# ELEKTRA-PMIC_v0_2-Half_frame_shield_for_.net
KiCad netlist of a schematic drawn in EAGLE
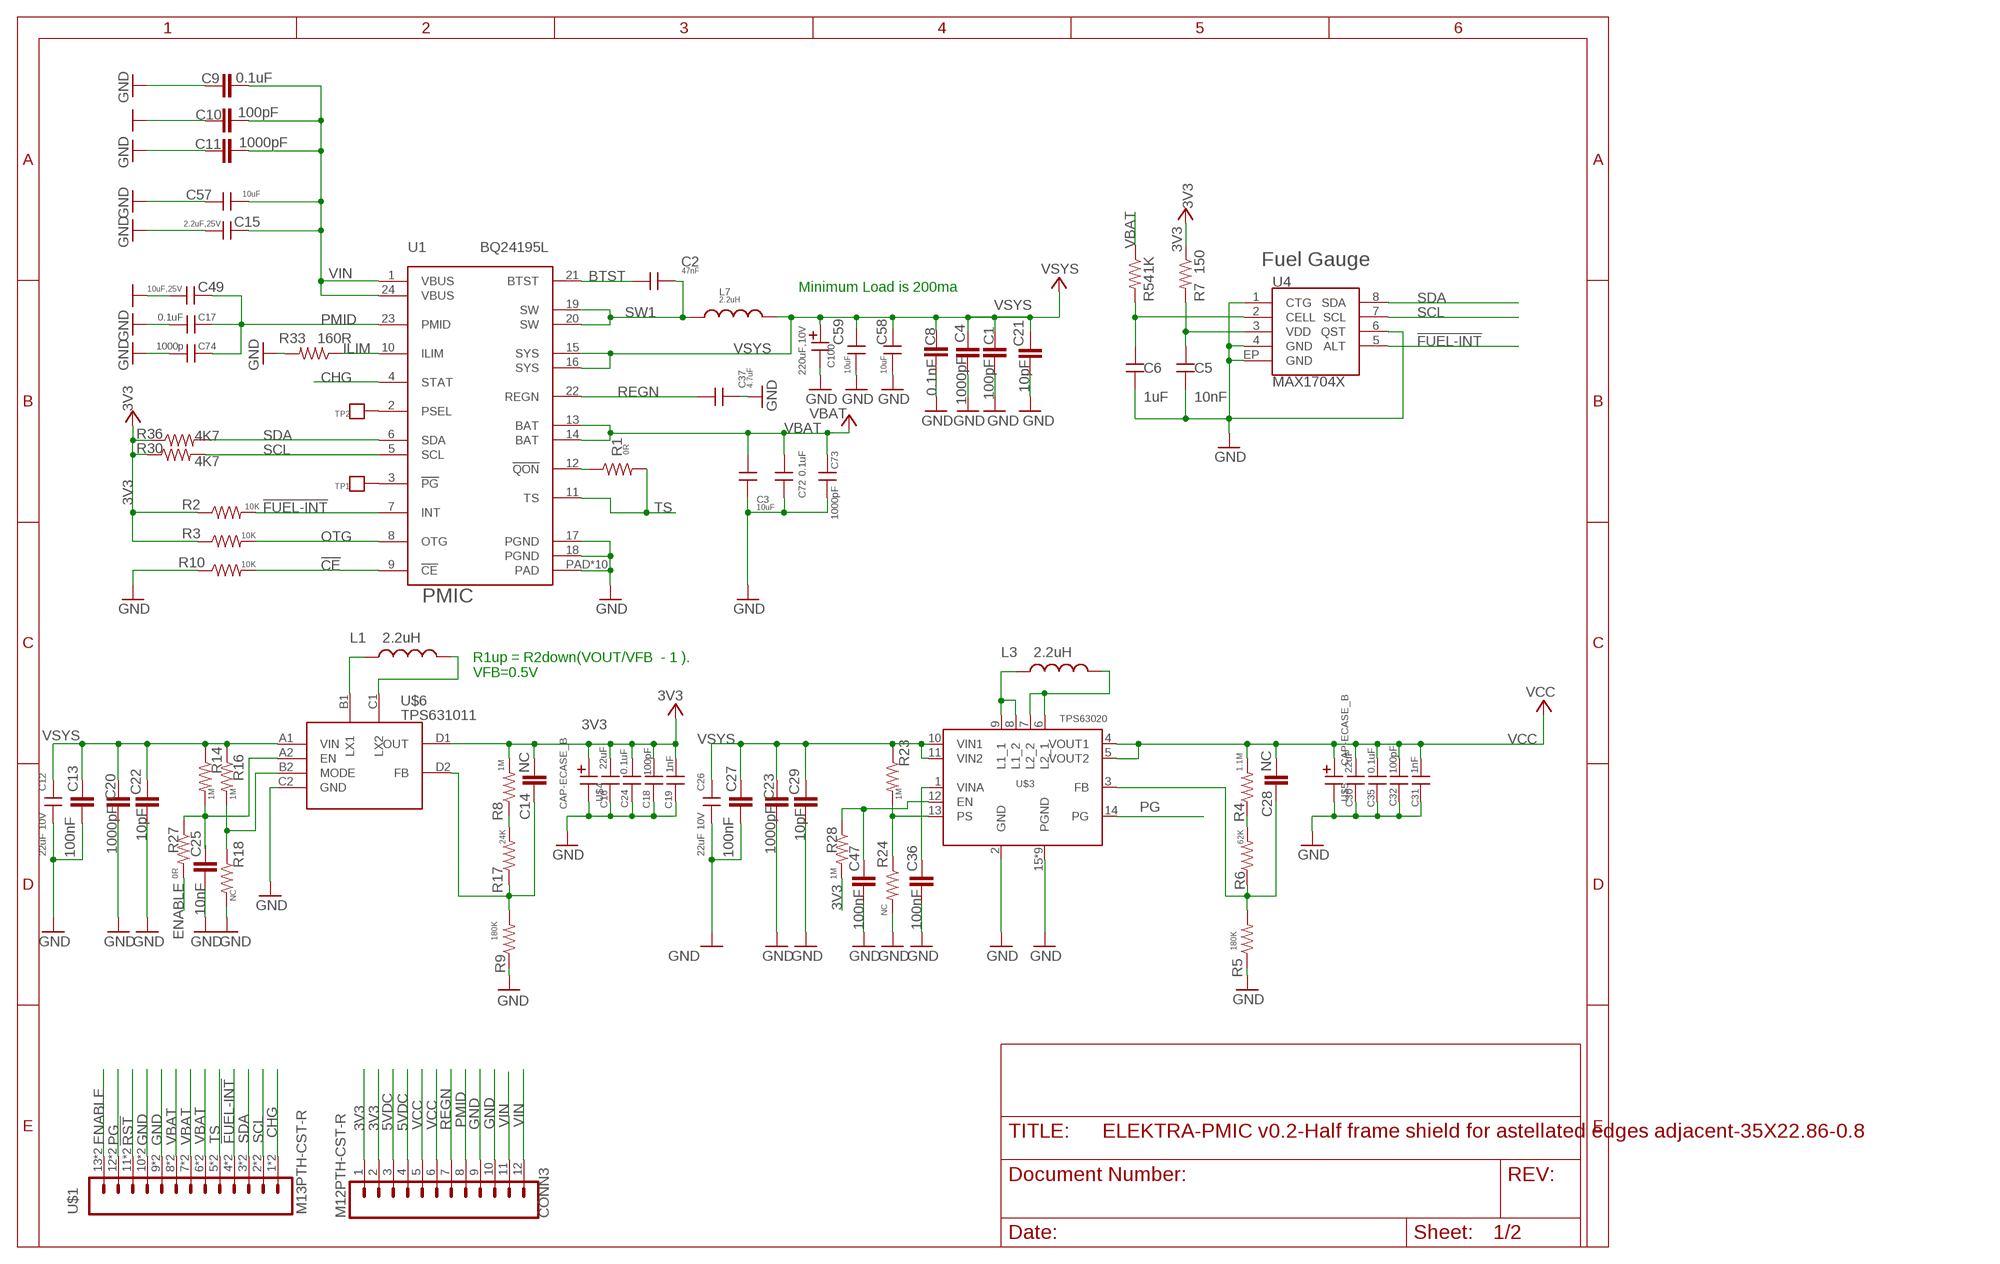
[diagram p0: schematic, sheet 1]

(export (version "E")
  (design (tool "Eeschema 10.0.6"))
  (components
    (comp (ref "C1")
      (value "100pF")
      (footprint "eagle-import:C0402_B")
      (libsource (lib "eagle-import") (part "CAP_1"))
    )
    (comp (ref "C2")
      (value "47nF")
      (footprint "eagle-import:C-0402")
      (libsource (lib "eagle-import") (part "particle SZ_CAP0402"))
    )
    (comp (ref "C3")
      (value "10uF")
      (footprint "eagle-import:C0603")
      (libsource (lib "eagle-import") (part "particle SZ_CAPC0603"))
    )
    (comp (ref "C4")
      (value "1000pF")
      (footprint "eagle-import:C0402_B")
      (libsource (lib "eagle-import") (part "CAP_1"))
    )
    (comp (ref "C5")
      (value "10nF")
      (footprint "eagle-import:C0402")
      (libsource (lib "eagle-import") (part "particle SZ_CAP0402A"))
    )
    (comp (ref "C6")
      (value "1uF")
      (footprint "eagle-import:C0402")
      (libsource (lib "eagle-import") (part "particle SZ_CAP0402A"))
    )
    (comp (ref "C8")
      (value "0.1nF")
      (footprint "eagle-import:C0402_B")
      (libsource (lib "eagle-import") (part "CAP_1"))
    )
    (comp (ref "C9")
      (value "0.1uF")
      (footprint "eagle-import:C0402_B")
      (libsource (lib "eagle-import") (part "CAP_1"))
    )
    (comp (ref "C10")
      (value "100pF")
      (footprint "eagle-import:C0402_B")
      (libsource (lib "eagle-import") (part "CAP_1"))
    )
    (comp (ref "C11")
      (value "1000pF")
      (footprint "eagle-import:C0402_B")
      (libsource (lib "eagle-import") (part "CAP_1"))
    )
    (comp (ref "C12")
      (value "22uF 10V")
      (footprint "eagle-import:C0805")
      (libsource (lib "eagle-import") (part "particle SZ_21650216_CAPC0805"))
    )
    (comp (ref "C13")
      (value "100nF")
      (footprint "eagle-import:C0402_B")
      (libsource (lib "eagle-import") (part "CAP_1"))
    )
    (comp (ref "C14")
      (value "NC")
      (footprint "eagle-import:C0402_B")
      (libsource (lib "eagle-import") (part "CAP_1"))
    )
    (comp (ref "C15")
      (value "2.2uF,25V")
      (footprint "eagle-import:C-0603A")
      (libsource (lib "eagle-import") (part "particle SZ_CAP0603A"))
    )
    (comp (ref "C16")
      (value "22uF")
      (footprint "eagle-import:C-0603A")
      (libsource (lib "eagle-import") (part "particle SZ_21650216_CAP0603A"))
    )
    (comp (ref "C17")
      (value "0.1uF")
      (footprint "eagle-import:C0402")
      (libsource (lib "eagle-import") (part "CAP0402A"))
    )
    (comp (ref "C18")
      (value "100pF")
      (footprint "eagle-import:C0402")
      (libsource (lib "eagle-import") (part "particle SZ_CAP0402A"))
    )
    (comp (ref "C19")
      (value "1nF")
      (footprint "eagle-import:C0402")
      (libsource (lib "eagle-import") (part "particle SZ_CAP0402A"))
    )
    (comp (ref "C20")
      (value "1000pF")
      (footprint "eagle-import:C0402_B")
      (libsource (lib "eagle-import") (part "CAP_1"))
    )
    (comp (ref "C21")
      (value "10pF")
      (footprint "eagle-import:C0402_B")
      (libsource (lib "eagle-import") (part "CAP_1"))
    )
    (comp (ref "C22")
      (value "10pF")
      (footprint "eagle-import:C0402_B")
      (libsource (lib "eagle-import") (part "CAP_1"))
    )
    (comp (ref "C23")
      (value "1000pF")
      (footprint "eagle-import:C0402_B")
      (libsource (lib "eagle-import") (part "CAP_1"))
    )
    (comp (ref "C24")
      (value "0.1uF")
      (footprint "eagle-import:C0402")
      (libsource (lib "eagle-import") (part "particle SZ_CAP0402A"))
    )
    (comp (ref "C25")
      (value "10nF")
      (footprint "eagle-import:C0402_B")
      (libsource (lib "eagle-import") (part "CAP_1"))
    )
    (comp (ref "C26")
      (value "22uF 10V")
      (footprint "eagle-import:C0805")
      (libsource (lib "eagle-import") (part "particle SZ_21650216_CAPC0805"))
    )
    (comp (ref "C27")
      (value "100nF")
      (footprint "eagle-import:C0402_B")
      (libsource (lib "eagle-import") (part "CAP_1"))
    )
    (comp (ref "C28")
      (value "NC")
      (footprint "eagle-import:C0402_B")
      (libsource (lib "eagle-import") (part "CAP_1"))
    )
    (comp (ref "C29")
      (value "10pF")
      (footprint "eagle-import:C0402_B")
      (libsource (lib "eagle-import") (part "CAP_1"))
    )
    (comp (ref "C30")
      (value "22uF")
      (footprint "eagle-import:C-0603A")
      (libsource (lib "eagle-import") (part "particle SZ_21650216_CAP0603A"))
    )
    (comp (ref "C31")
      (value "1nF")
      (footprint "eagle-import:C0402")
      (libsource (lib "eagle-import") (part "particle SZ_CAP0402A"))
    )
    (comp (ref "C32")
      (value "100pF")
      (footprint "eagle-import:C0402")
      (libsource (lib "eagle-import") (part "particle SZ_CAP0402A"))
    )
    (comp (ref "C35")
      (value "0.1uF")
      (footprint "eagle-import:C0402")
      (libsource (lib "eagle-import") (part "particle SZ_CAP0402A"))
    )
    (comp (ref "C36")
      (value "100nF")
      (footprint "eagle-import:C0402_B")
      (libsource (lib "eagle-import") (part "CAP_1"))
    )
    (comp (ref "C37")
      (value "4.7uF")
      (footprint "eagle-import:C0402")
      (libsource (lib "eagle-import") (part "particle SZ_CAP0402A"))
    )
    (comp (ref "C47")
      (value "100nF")
      (footprint "eagle-import:C0402_B")
      (libsource (lib "eagle-import") (part "CAP_1"))
    )
    (comp (ref "C49")
      (value "10uF,25V")
      (footprint "eagle-import:C-0603A")
      (libsource (lib "eagle-import") (part "particle SZ_CAP0603A"))
    )
    (comp (ref "C57")
      (value "10uF")
      (footprint "eagle-import:C-0603A")
      (libsource (lib "eagle-import") (part "particle SZ_CAP0603A"))
    )
    (comp (ref "C58")
      (value "10uF")
      (footprint "eagle-import:C-0603A")
      (libsource (lib "eagle-import") (part "particle SZ_CAP0603A"))
    )
    (comp (ref "C59")
      (value "10uF")
      (footprint "eagle-import:C-0603A")
      (libsource (lib "eagle-import") (part "particle SZ_CAP0603A"))
    )
    (comp (ref "C72")
      (value "0.1uF")
      (footprint "eagle-import:C-0402")
      (libsource (lib "eagle-import") (part "particle SZ_CAP0402"))
    )
    (comp (ref "C73")
      (value "1000pF")
      (footprint "eagle-import:C-0402")
      (libsource (lib "eagle-import") (part "particle SZ_CAP0402"))
    )
    (comp (ref "C74")
      (value "1000p")
      (footprint "eagle-import:C-0402")
      (libsource (lib "eagle-import") (part "particle SZ_CAP0402"))
    )
    (comp (ref "C100")
      (value "220uF,10V")
      (footprint "eagle-import:CASE-B")
      (libsource (lib "eagle-import") (part "CAP-ECASE_B"))
    )
    (comp (ref "CONN3")
      (value "M12PTH-CST-R")
      (footprint "eagle-import:1X12-CASTELLATED")
      (libsource (lib "eagle-import") (part "M12PTH-CST-R"))
    )
    (comp (ref "L1")
      (value "2.2uH")
      (footprint "eagle-import:INDUCTOR-VLS-E")
      (libsource (lib "eagle-import") (part "INDUCTOR-SPARKFUNVLS3012ET-4R7M"))
    )
    (comp (ref "L3")
      (value "2.2uH")
      (footprint "eagle-import:INDUCTOR-VLS-E")
      (libsource (lib "eagle-import") (part "INDUCTOR-SPARKFUNVLS3012ET-4R7M"))
    )
    (comp (ref "L7")
      (value "2.2uH")
      (footprint "eagle-import:INDUCTOR-4040")
      (libsource (lib "eagle-import") (part "INDUCTORI"))
    )
    (comp (ref "R1")
      (value "0R")
      (footprint "eagle-import:R0402_B")
      (libsource (lib "eagle-import") (part "Spark_R-US_"))
    )
    (comp (ref "R2")
      (value "10K")
      (footprint "eagle-import:R0402_B")
      (libsource (lib "eagle-import") (part "Spark_R-US_"))
    )
    (comp (ref "R3")
      (value "10K")
      (footprint "eagle-import:R0402_B")
      (libsource (lib "eagle-import") (part "Spark_R-US_"))
    )
    (comp (ref "R4")
      (value "1.1M")
      (footprint "eagle-import:R0402_B")
      (libsource (lib "eagle-import") (part "Spark_R-US_"))
    )
    (comp (ref "R5")
      (value "180K")
      (footprint "eagle-import:R0402_B")
      (libsource (lib "eagle-import") (part "Spark_R-US_"))
    )
    (comp (ref "R6")
      (value "62K")
      (footprint "eagle-import:R0402_B")
      (libsource (lib "eagle-import") (part "Spark_R-US_"))
    )
    (comp (ref "R7")
      (value "150")
      (footprint "eagle-import:R0402_B")
      (libsource (lib "eagle-import") (part "R-US_"))
    )
    (comp (ref "R8")
      (value "1M")
      (footprint "eagle-import:R0402_B")
      (libsource (lib "eagle-import") (part "Spark_R-US_"))
    )
    (comp (ref "R9")
      (value "180K")
      (footprint "eagle-import:R0402_B")
      (libsource (lib "eagle-import") (part "Spark_R-US_"))
    )
    (comp (ref "R10")
      (value "10K")
      (footprint "eagle-import:R0402_B")
      (libsource (lib "eagle-import") (part "Spark_R-US_"))
    )
    (comp (ref "R14")
      (value "1M")
      (footprint "eagle-import:R0402_B")
      (libsource (lib "eagle-import") (part "Spark_R-US_"))
    )
    (comp (ref "R16")
      (value "1M")
      (footprint "eagle-import:R0402_B")
      (libsource (lib "eagle-import") (part "Spark_R-US_"))
    )
    (comp (ref "R17")
      (value "24K")
      (footprint "eagle-import:R0402_B")
      (libsource (lib "eagle-import") (part "Spark_R-US_"))
    )
    (comp (ref "R18")
      (value "NC")
      (footprint "eagle-import:R0402_B")
      (libsource (lib "eagle-import") (part "Spark_R-US_"))
    )
    (comp (ref "R23")
      (value "1M")
      (footprint "eagle-import:R0402_B")
      (libsource (lib "eagle-import") (part "Spark_R-US_"))
    )
    (comp (ref "R24")
      (value "NC")
      (footprint "eagle-import:R0402_B")
      (libsource (lib "eagle-import") (part "Spark_R-US_"))
    )
    (comp (ref "R27")
      (value "0R")
      (footprint "eagle-import:R0402_B")
      (libsource (lib "eagle-import") (part "Spark_R-US_"))
    )
    (comp (ref "R28")
      (value "1M")
      (footprint "eagle-import:R0402_B")
      (libsource (lib "eagle-import") (part "Spark_R-US_"))
    )
    (comp (ref "R30")
      (value "4K7")
      (footprint "eagle-import:R0402_B")
      (libsource (lib "eagle-import") (part "R-US_"))
    )
    (comp (ref "R33")
      (value "160R")
      (footprint "eagle-import:R0402_B")
      (libsource (lib "eagle-import") (part "R-US_"))
    )
    (comp (ref "R36")
      (value "4K7")
      (footprint "eagle-import:R0402_B")
      (libsource (lib "eagle-import") (part "R-US_"))
    )
    (comp (ref "R54")
      (value "1K")
      (footprint "eagle-import:R0402_B")
      (libsource (lib "eagle-import") (part "R-US_"))
    )
    (comp (ref "TP1")
      (value "TP")
      (footprint "eagle-import:TP0.7MM")
      (libsource (lib "eagle-import") (part "TP"))
    )
    (comp (ref "TP2")
      (value "TP")
      (footprint "eagle-import:TP0.7MM")
      (libsource (lib "eagle-import") (part "TP"))
    )
    (comp (ref "U$1")
      (value "M13PTH-CST-R")
      (footprint "eagle-import:1X13-CASTELLATED")
      (libsource (lib "eagle-import") (part "M13PTH-CST-R"))
    )
    (comp (ref "U$3")
      (value "TPS63020")
      (footprint "eagle-import:TPS63020")
      (libsource (lib "eagle-import") (part "TPS63020"))
    )
    (comp (ref "U$4")
      (value "CAP-ECASE_B")
      (footprint "eagle-import:CASE-B")
      (libsource (lib "eagle-import") (part "CAP-ECASE_B"))
    )
    (comp (ref "U$5")
      (value "CAP-ECASE_B")
      (footprint "eagle-import:CASE-B")
      (libsource (lib "eagle-import") (part "CAP-ECASE_B"))
    )
    (comp (ref "U$6")
      (value "TPS631011")
      (footprint "eagle-import:DSBGA")
      (libsource (lib "eagle-import") (part "TPS631010"))
    )
    (comp (ref "U1")
      (value "BQ24195L")
      (footprint "eagle-import:QFN24")
      (libsource (lib "eagle-import") (part "BQ24298RTWR"))
    )
    (comp (ref "U4")
      (value "MAX1704X")
      (footprint "eagle-import:TDFN-8")
      (libsource (lib "eagle-import") (part "MAX1704X"))
    )
  )
  (nets
    (net (code "1") (name "3V3") (class "Default")
      (node (ref "C14") (pin "2") (pinfunction "P$2_2") (pintype "passive"))
      (node (ref "C16") (pin "1") (pinfunction "1_1") (pintype "bidirectional"))
      (node (ref "C18") (pin "1") (pinfunction "1_1") (pintype "bidirectional"))
      (node (ref "C19") (pin "1") (pinfunction "1_1") (pintype "bidirectional"))
      (node (ref "C24") (pin "1") (pinfunction "1_1") (pintype "bidirectional"))
      (node (ref "CONN3") (pin "1") (pinfunction "1_1") (pintype "passive"))
      (node (ref "CONN3") (pin "2") (pinfunction "2_2") (pintype "passive"))
      (node (ref "R2") (pin "1") (pinfunction "1_1") (pintype "passive"))
      (node (ref "R28") (pin "2") (pinfunction "2_2") (pintype "passive"))
      (node (ref "R3") (pin "1") (pinfunction "1_1") (pintype "passive"))
      (node (ref "R30") (pin "1") (pinfunction "1_1") (pintype "passive"))
      (node (ref "R36") (pin "1") (pinfunction "1_1") (pintype "passive"))
      (node (ref "R7") (pin "1") (pinfunction "1_1") (pintype "passive"))
      (node (ref "R8") (pin "2") (pinfunction "2_2") (pintype "passive"))
      (node (ref "U$4") (pin "P$1") (pinfunction "1_P$1") (pintype "bidirectional"))
      (node (ref "U$6") (pin "D1") (pinfunction "OUT_D1") (pintype "bidirectional"))
    )
    (net (code "2") (name "5VDC") (class "Default")
      (node (ref "CONN3") (pin "3") (pinfunction "3_3") (pintype "passive"))
      (node (ref "CONN3") (pin "4") (pinfunction "4_4") (pintype "passive"))
    )
    (net (code "3") (name "BTST") (class "Default")
      (node (ref "C2") (pin "1") (pinfunction "1_1") (pintype "bidirectional"))
      (node (ref "U1") (pin "21") (pinfunction "BTST_21") (pintype "bidirectional"))
    )
    (net (code "4") (name "CHG") (class "Default")
      (node (ref "U$1") (pin "1") (pinfunction "1_1") (pintype "passive"))
      (node (ref "U$1") (pin "@1") (pinfunction "1_@1") (pintype "passive"))
      (node (ref "U1") (pin "4") (pinfunction "STAT_4") (pintype "bidirectional"))
    )
    (net (code "5") (name "ENABLE") (class "Default")
      (node (ref "R27") (pin "2") (pinfunction "2_2") (pintype "passive"))
      (node (ref "U$1") (pin "13") (pinfunction "13_13") (pintype "passive"))
      (node (ref "U$1") (pin "@13") (pinfunction "13_@13") (pintype "passive"))
    )
    (net (code "6") (name "GND") (class "Default")
      (node (ref "C1") (pin "1") (pinfunction "P$1_1") (pintype "passive"))
      (node (ref "C10") (pin "1") (pinfunction "P$1_1") (pintype "passive"))
      (node (ref "C100") (pin "P$2") (pinfunction "2_P$2") (pintype "bidirectional"))
      (node (ref "C11") (pin "1") (pinfunction "P$1_1") (pintype "passive"))
      (node (ref "C12") (pin "2") (pinfunction "2_2") (pintype "bidirectional"))
      (node (ref "C13") (pin "1") (pinfunction "P$1_1") (pintype "passive"))
      (node (ref "C15") (pin "2") (pinfunction "2_2") (pintype "bidirectional"))
      (node (ref "C16") (pin "2") (pinfunction "2_2") (pintype "bidirectional"))
      (node (ref "C17") (pin "1") (pinfunction "1_1") (pintype "bidirectional"))
      (node (ref "C18") (pin "2") (pinfunction "2_2") (pintype "bidirectional"))
      (node (ref "C19") (pin "2") (pinfunction "2_2") (pintype "bidirectional"))
      (node (ref "C20") (pin "1") (pinfunction "P$1_1") (pintype "passive"))
      (node (ref "C21") (pin "1") (pinfunction "P$1_1") (pintype "passive"))
      (node (ref "C22") (pin "1") (pinfunction "P$1_1") (pintype "passive"))
      (node (ref "C23") (pin "1") (pinfunction "P$1_1") (pintype "passive"))
      (node (ref "C24") (pin "2") (pinfunction "2_2") (pintype "bidirectional"))
      (node (ref "C25") (pin "1") (pinfunction "P$1_1") (pintype "passive"))
      (node (ref "C26") (pin "2") (pinfunction "2_2") (pintype "bidirectional"))
      (node (ref "C27") (pin "1") (pinfunction "P$1_1") (pintype "passive"))
      (node (ref "C29") (pin "1") (pinfunction "P$1_1") (pintype "passive"))
      (node (ref "C3") (pin "2") (pinfunction "2_2") (pintype "bidirectional"))
      (node (ref "C30") (pin "2") (pinfunction "2_2") (pintype "bidirectional"))
      (node (ref "C31") (pin "2") (pinfunction "2_2") (pintype "bidirectional"))
      (node (ref "C32") (pin "2") (pinfunction "2_2") (pintype "bidirectional"))
      (node (ref "C35") (pin "2") (pinfunction "2_2") (pintype "bidirectional"))
      (node (ref "C36") (pin "1") (pinfunction "P$1_1") (pintype "passive"))
      (node (ref "C37") (pin "2") (pinfunction "2_2") (pintype "bidirectional"))
      (node (ref "C4") (pin "1") (pinfunction "P$1_1") (pintype "passive"))
      (node (ref "C47") (pin "1") (pinfunction "P$1_1") (pintype "passive"))
      (node (ref "C49") (pin "2") (pinfunction "2_2") (pintype "bidirectional"))
      (node (ref "C5") (pin "2") (pinfunction "2_2") (pintype "bidirectional"))
      (node (ref "C57") (pin "2") (pinfunction "2_2") (pintype "bidirectional"))
      (node (ref "C58") (pin "2") (pinfunction "2_2") (pintype "bidirectional"))
      (node (ref "C59") (pin "2") (pinfunction "2_2") (pintype "bidirectional"))
      (node (ref "C6") (pin "2") (pinfunction "2_2") (pintype "bidirectional"))
      (node (ref "C72") (pin "2") (pinfunction "2_2") (pintype "bidirectional"))
      (node (ref "C73") (pin "2") (pinfunction "2_2") (pintype "bidirectional"))
      (node (ref "C74") (pin "1") (pinfunction "1_1") (pintype "bidirectional"))
      (node (ref "C8") (pin "1") (pinfunction "P$1_1") (pintype "passive"))
      (node (ref "C9") (pin "1") (pinfunction "P$1_1") (pintype "passive"))
      (node (ref "CONN3") (pin "10") (pinfunction "10_10") (pintype "passive"))
      (node (ref "CONN3") (pin "9") (pinfunction "9_9") (pintype "passive"))
      (node (ref "R10") (pin "1") (pinfunction "1_1") (pintype "passive"))
      (node (ref "R18") (pin "2") (pinfunction "2_2") (pintype "passive"))
      (node (ref "R24") (pin "2") (pinfunction "2_2") (pintype "passive"))
      (node (ref "R33") (pin "2") (pinfunction "2_2") (pintype "passive"))
      (node (ref "R5") (pin "1") (pinfunction "1_1") (pintype "passive"))
      (node (ref "R9") (pin "1") (pinfunction "1_1") (pintype "passive"))
      (node (ref "U$1") (pin "10") (pinfunction "10_10") (pintype "passive"))
      (node (ref "U$1") (pin "9") (pinfunction "9_9") (pintype "passive"))
      (node (ref "U$1") (pin "@10") (pinfunction "10_@10") (pintype "passive"))
      (node (ref "U$1") (pin "@9") (pinfunction "9_@9") (pintype "passive"))
      (node (ref "U$3") (pin "15") (pinfunction "PGND_15") (pintype "bidirectional"))
      (node (ref "U$3") (pin "16") (pinfunction "PGND_16") (pintype "bidirectional"))
      (node (ref "U$3") (pin "17") (pinfunction "PGND_17") (pintype "bidirectional"))
      (node (ref "U$3") (pin "18") (pinfunction "PGND_18") (pintype "bidirectional"))
      (node (ref "U$3") (pin "19") (pinfunction "PGND_19") (pintype "bidirectional"))
      (node (ref "U$3") (pin "2") (pinfunction "GND_2") (pintype "bidirectional"))
      (node (ref "U$3") (pin "20") (pinfunction "PGND_20") (pintype "bidirectional"))
      (node (ref "U$3") (pin "21") (pinfunction "PGND_21") (pintype "bidirectional"))
      (node (ref "U$3") (pin "22") (pinfunction "PGND_22") (pintype "bidirectional"))
      (node (ref "U$3") (pin "23") (pinfunction "PGND_23") (pintype "bidirectional"))
      (node (ref "U$4") (pin "P$2") (pinfunction "2_P$2") (pintype "bidirectional"))
      (node (ref "U$5") (pin "P$2") (pinfunction "2_P$2") (pintype "bidirectional"))
      (node (ref "U$6") (pin "C2") (pinfunction "GND_C2") (pintype "bidirectional"))
      (node (ref "U1") (pin "17") (pinfunction "PGND_17") (pintype "passive"))
      (node (ref "U1") (pin "18") (pinfunction "PGND_18") (pintype "passive"))
      (node (ref "U1") (pin "PAD") (pinfunction "PAD_PAD") (pintype "power_in"))
      (node (ref "U1") (pin "PAD@1") (pinfunction "PAD_PAD@1") (pintype "power_in"))
      (node (ref "U1") (pin "PAD@2") (pinfunction "PAD_PAD@2") (pintype "power_in"))
      (node (ref "U1") (pin "PAD@3") (pinfunction "PAD_PAD@3") (pintype "power_in"))
      (node (ref "U1") (pin "PAD@4") (pinfunction "PAD_PAD@4") (pintype "power_in"))
      (node (ref "U1") (pin "PAD@5") (pinfunction "PAD_PAD@5") (pintype "power_in"))
      (node (ref "U1") (pin "PAD@6") (pinfunction "PAD_PAD@6") (pintype "power_in"))
      (node (ref "U1") (pin "PAD@7") (pinfunction "PAD_PAD@7") (pintype "power_in"))
      (node (ref "U1") (pin "PAD@8") (pinfunction "PAD_PAD@8") (pintype "power_in"))
      (node (ref "U1") (pin "PAD@9") (pinfunction "PAD_PAD@9") (pintype "power_in"))
      (node (ref "U4") (pin "1") (pinfunction "CTG_1") (pintype "bidirectional"))
      (node (ref "U4") (pin "4") (pinfunction "GND_4") (pintype "bidirectional"))
      (node (ref "U4") (pin "6") (pinfunction "QST_6") (pintype "bidirectional"))
      (node (ref "U4") (pin "EP") (pinfunction "GND_EP") (pintype "bidirectional"))
    )
    (net (code "7") (name "ILIM") (class "Default")
      (node (ref "R33") (pin "1") (pinfunction "1_1") (pintype "passive"))
      (node (ref "U1") (pin "10") (pinfunction "ILIM_10") (pintype "output"))
    )
    (net (code "8") (name "Net-(C14-P$1)") (class "Default")
      (node (ref "C14") (pin "1") (pinfunction "P$1_1") (pintype "passive"))
      (node (ref "R17") (pin "1") (pinfunction "1_1") (pintype "passive"))
      (node (ref "R9") (pin "2") (pinfunction "2_2") (pintype "passive"))
      (node (ref "U$6") (pin "D2") (pinfunction "FB_D2") (pintype "bidirectional"))
    )
    (net (code "9") (name "Net-(C25-P$2)") (class "Default")
      (node (ref "C25") (pin "2") (pinfunction "P$2_2") (pintype "passive"))
      (node (ref "R14") (pin "2") (pinfunction "2_2") (pintype "passive"))
      (node (ref "R27") (pin "1") (pinfunction "1_1") (pintype "passive"))
      (node (ref "U$6") (pin "A2") (pinfunction "EN_A2") (pintype "bidirectional"))
    )
    (net (code "10") (name "Net-(C28-P$1)") (class "Default")
      (node (ref "C28") (pin "1") (pinfunction "P$1_1") (pintype "passive"))
      (node (ref "R5") (pin "2") (pinfunction "2_2") (pintype "passive"))
      (node (ref "R6") (pin "1") (pinfunction "1_1") (pintype "passive"))
      (node (ref "U$3") (pin "3") (pinfunction "FB_3") (pintype "bidirectional"))
    )
    (net (code "11") (name "Net-(C36-P$2)") (class "Default")
      (node (ref "C36") (pin "2") (pinfunction "P$2_2") (pintype "passive"))
      (node (ref "U$3") (pin "1") (pinfunction "VINA_1") (pintype "bidirectional"))
    )
    (net (code "12") (name "Net-(C47-P$2)") (class "Default")
      (node (ref "C47") (pin "2") (pinfunction "P$2_2") (pintype "passive"))
      (node (ref "R28") (pin "1") (pinfunction "1_1") (pintype "passive"))
      (node (ref "U$3") (pin "12") (pinfunction "EN_12") (pintype "bidirectional"))
    )
    (net (code "13") (name "Net-(L1-1)") (class "Default")
      (node (ref "L1") (pin "P$1") (pinfunction "1_P$1") (pintype "passive"))
      (node (ref "U$6") (pin "B1") (pinfunction "LX1_B1") (pintype "bidirectional"))
    )
    (net (code "14") (name "Net-(L1-2)") (class "Default")
      (node (ref "L1") (pin "P$2") (pinfunction "2_P$2") (pintype "passive"))
      (node (ref "U$6") (pin "C1") (pinfunction "LX2_C1") (pintype "bidirectional"))
    )
    (net (code "15") (name "Net-(L3-1)") (class "Default")
      (node (ref "L3") (pin "P$1") (pinfunction "1_P$1") (pintype "passive"))
      (node (ref "U$3") (pin "8") (pinfunction "L1_2_8") (pintype "bidirectional"))
      (node (ref "U$3") (pin "9") (pinfunction "L1_1_9") (pintype "bidirectional"))
    )
    (net (code "16") (name "Net-(L3-2)") (class "Default")
      (node (ref "L3") (pin "P$2") (pinfunction "2_P$2") (pintype "passive"))
      (node (ref "U$3") (pin "6") (pinfunction "L2_1_6") (pintype "bidirectional"))
      (node (ref "U$3") (pin "7") (pinfunction "L2_2_7") (pintype "bidirectional"))
    )
    (net (code "17") (name "Net-(R4-Pad1)") (class "Default")
      (node (ref "R4") (pin "1") (pinfunction "1_1") (pintype "passive"))
      (node (ref "R6") (pin "2") (pinfunction "2_2") (pintype "passive"))
    )
    (net (code "18") (name "Net-(R17-Pad2)") (class "Default")
      (node (ref "R17") (pin "2") (pinfunction "2_2") (pintype "passive"))
      (node (ref "R8") (pin "1") (pinfunction "1_1") (pintype "passive"))
    )
    (net (code "19") (name "Net-(TP1-1)") (class "Default")
      (node (ref "TP1") (pin "P$1") (pinfunction "1_P$1") (pintype "bidirectional"))
      (node (ref "U1") (pin "3") (pinfunction "~{PG}_3") (pintype "output"))
    )
    (net (code "20") (name "Net-(TP2-1)") (class "Default")
      (node (ref "TP2") (pin "P$1") (pinfunction "1_P$1") (pintype "bidirectional"))
      (node (ref "U1") (pin "2") (pinfunction "PSEL_2") (pintype "output"))
    )
    (net (code "21") (name "Net-(U$3-PS)") (class "Default")
      (node (ref "R23") (pin "2") (pinfunction "2_2") (pintype "passive"))
      (node (ref "R24") (pin "1") (pinfunction "1_1") (pintype "passive"))
      (node (ref "U$3") (pin "13") (pinfunction "PS_13") (pintype "bidirectional"))
    )
    (net (code "22") (name "Net-(U$6-MODE)") (class "Default")
      (node (ref "R16") (pin "2") (pinfunction "2_2") (pintype "passive"))
      (node (ref "R18") (pin "1") (pinfunction "1_1") (pintype "passive"))
      (node (ref "U$6") (pin "B2") (pinfunction "MODE_B2") (pintype "bidirectional"))
    )
    (net (code "23") (name "Net-(U1-~{QON})") (class "Default")
      (node (ref "R1") (pin "1") (pinfunction "1_1") (pintype "passive"))
      (node (ref "U1") (pin "12") (pinfunction "~{QON}_12") (pintype "bidirectional"))
    )
    (net (code "24") (name "Net-(U4-CELL)") (class "Default")
      (node (ref "C6") (pin "1") (pinfunction "1_1") (pintype "bidirectional"))
      (node (ref "R54") (pin "2") (pinfunction "2_2") (pintype "passive"))
      (node (ref "U4") (pin "2") (pinfunction "CELL_2") (pintype "bidirectional"))
    )
    (net (code "25") (name "Net-(U4-VDD)") (class "Default")
      (node (ref "C5") (pin "1") (pinfunction "1_1") (pintype "bidirectional"))
      (node (ref "R7") (pin "2") (pinfunction "2_2") (pintype "passive"))
      (node (ref "U4") (pin "3") (pinfunction "VDD_3") (pintype "bidirectional"))
    )
    (net (code "26") (name "OTG") (class "Default")
      (node (ref "R3") (pin "2") (pinfunction "2_2") (pintype "passive"))
      (node (ref "U1") (pin "8") (pinfunction "OTG_8") (pintype "bidirectional"))
    )
    (net (code "27") (name "PG") (class "Default")
      (node (ref "U$1") (pin "12") (pinfunction "12_12") (pintype "passive"))
      (node (ref "U$1") (pin "@12") (pinfunction "12_@12") (pintype "passive"))
      (node (ref "U$3") (pin "14") (pinfunction "PG_14") (pintype "bidirectional"))
    )
    (net (code "28") (name "PMID") (class "Default")
      (node (ref "C17") (pin "2") (pinfunction "2_2") (pintype "bidirectional"))
      (node (ref "C49") (pin "1") (pinfunction "1_1") (pintype "bidirectional"))
      (node (ref "C74") (pin "2") (pinfunction "2_2") (pintype "bidirectional"))
      (node (ref "CONN3") (pin "8") (pinfunction "8_8") (pintype "passive"))
      (node (ref "U1") (pin "23") (pinfunction "PMID_23") (pintype "passive"))
    )
    (net (code "29") (name "REGN") (class "Default")
      (node (ref "C37") (pin "1") (pinfunction "1_1") (pintype "bidirectional"))
      (node (ref "CONN3") (pin "7") (pinfunction "7_7") (pintype "passive"))
      (node (ref "U1") (pin "22") (pinfunction "REGN_22") (pintype "bidirectional"))
    )
    (net (code "30") (name "SCL") (class "Default")
      (node (ref "R30") (pin "2") (pinfunction "2_2") (pintype "passive"))
      (node (ref "U$1") (pin "2") (pinfunction "2_2") (pintype "passive"))
      (node (ref "U$1") (pin "@2") (pinfunction "2_@2") (pintype "passive"))
      (node (ref "U1") (pin "5") (pinfunction "SCL_5") (pintype "output"))
      (node (ref "U4") (pin "7") (pinfunction "SCL_7") (pintype "bidirectional"))
    )
    (net (code "31") (name "SDA") (class "Default")
      (node (ref "R36") (pin "2") (pinfunction "2_2") (pintype "passive"))
      (node (ref "U$1") (pin "3") (pinfunction "3_3") (pintype "passive"))
      (node (ref "U$1") (pin "@3") (pinfunction "3_@3") (pintype "passive"))
      (node (ref "U1") (pin "6") (pinfunction "SDA_6") (pintype "bidirectional"))
      (node (ref "U4") (pin "8") (pinfunction "SDA_8") (pintype "bidirectional"))
    )
    (net (code "32") (name "SW1") (class "Default")
      (node (ref "C2") (pin "2") (pinfunction "2_2") (pintype "bidirectional"))
      (node (ref "L7") (pin "P$1") (pinfunction "1_P$1") (pintype "passive"))
      (node (ref "U1") (pin "19") (pinfunction "SW_19") (pintype "power_in"))
      (node (ref "U1") (pin "20") (pinfunction "SW_20") (pintype "power_in"))
    )
    (net (code "33") (name "TS") (class "Default")
      (node (ref "R1") (pin "2") (pinfunction "2_2") (pintype "passive"))
      (node (ref "U$1") (pin "5") (pinfunction "5_5") (pintype "passive"))
      (node (ref "U$1") (pin "@5") (pinfunction "5_@5") (pintype "passive"))
      (node (ref "U1") (pin "11") (pinfunction "TS_11") (pintype "bidirectional"))
    )
    (net (code "34") (name "VBAT") (class "Default")
      (node (ref "C3") (pin "1") (pinfunction "1_1") (pintype "bidirectional"))
      (node (ref "C72") (pin "1") (pinfunction "1_1") (pintype "bidirectional"))
      (node (ref "C73") (pin "1") (pinfunction "1_1") (pintype "bidirectional"))
      (node (ref "R54") (pin "1") (pinfunction "1_1") (pintype "passive"))
      (node (ref "U$1") (pin "6") (pinfunction "6_6") (pintype "passive"))
      (node (ref "U$1") (pin "7") (pinfunction "7_7") (pintype "passive"))
      (node (ref "U$1") (pin "8") (pinfunction "8_8") (pintype "passive"))
      (node (ref "U$1") (pin "@6") (pinfunction "6_@6") (pintype "passive"))
      (node (ref "U$1") (pin "@7") (pinfunction "7_@7") (pintype "passive"))
      (node (ref "U$1") (pin "@8") (pinfunction "8_@8") (pintype "passive"))
      (node (ref "U1") (pin "13") (pinfunction "BAT_13") (pintype "passive"))
      (node (ref "U1") (pin "14") (pinfunction "BAT_14") (pintype "power_in"))
    )
    (net (code "35") (name "VCC") (class "Default")
      (node (ref "C28") (pin "2") (pinfunction "P$2_2") (pintype "passive"))
      (node (ref "C30") (pin "1") (pinfunction "1_1") (pintype "bidirectional"))
      (node (ref "C31") (pin "1") (pinfunction "1_1") (pintype "bidirectional"))
      (node (ref "C32") (pin "1") (pinfunction "1_1") (pintype "bidirectional"))
      (node (ref "C35") (pin "1") (pinfunction "1_1") (pintype "bidirectional"))
      (node (ref "CONN3") (pin "5") (pinfunction "5_5") (pintype "passive"))
      (node (ref "CONN3") (pin "6") (pinfunction "6_6") (pintype "passive"))
      (node (ref "R4") (pin "2") (pinfunction "2_2") (pintype "passive"))
      (node (ref "U$3") (pin "4") (pinfunction "VOUT1_4") (pintype "bidirectional"))
      (node (ref "U$3") (pin "5") (pinfunction "VOUT2_5") (pintype "bidirectional"))
      (node (ref "U$5") (pin "P$1") (pinfunction "1_P$1") (pintype "bidirectional"))
    )
    (net (code "36") (name "VIN") (class "Default")
      (node (ref "C10") (pin "2") (pinfunction "P$2_2") (pintype "passive"))
      (node (ref "C11") (pin "2") (pinfunction "P$2_2") (pintype "passive"))
      (node (ref "C15") (pin "1") (pinfunction "1_1") (pintype "bidirectional"))
      (node (ref "C57") (pin "1") (pinfunction "1_1") (pintype "bidirectional"))
      (node (ref "C9") (pin "2") (pinfunction "P$2_2") (pintype "passive"))
      (node (ref "CONN3") (pin "11") (pinfunction "11_11") (pintype "passive"))
      (node (ref "CONN3") (pin "12") (pinfunction "12_12") (pintype "passive"))
      (node (ref "U1") (pin "1") (pinfunction "VBUS_1") (pintype "power_in"))
      (node (ref "U1") (pin "24") (pinfunction "VBUS_24") (pintype "passive"))
    )
    (net (code "37") (name "VSYS") (class "Default")
      (node (ref "C1") (pin "2") (pinfunction "P$2_2") (pintype "passive"))
      (node (ref "C100") (pin "P$1") (pinfunction "1_P$1") (pintype "bidirectional"))
      (node (ref "C12") (pin "1") (pinfunction "1_1") (pintype "bidirectional"))
      (node (ref "C13") (pin "2") (pinfunction "P$2_2") (pintype "passive"))
      (node (ref "C20") (pin "2") (pinfunction "P$2_2") (pintype "passive"))
      (node (ref "C21") (pin "2") (pinfunction "P$2_2") (pintype "passive"))
      (node (ref "C22") (pin "2") (pinfunction "P$2_2") (pintype "passive"))
      (node (ref "C23") (pin "2") (pinfunction "P$2_2") (pintype "passive"))
      (node (ref "C26") (pin "1") (pinfunction "1_1") (pintype "bidirectional"))
      (node (ref "C27") (pin "2") (pinfunction "P$2_2") (pintype "passive"))
      (node (ref "C29") (pin "2") (pinfunction "P$2_2") (pintype "passive"))
      (node (ref "C4") (pin "2") (pinfunction "P$2_2") (pintype "passive"))
      (node (ref "C58") (pin "1") (pinfunction "1_1") (pintype "bidirectional"))
      (node (ref "C59") (pin "1") (pinfunction "1_1") (pintype "bidirectional"))
      (node (ref "C8") (pin "2") (pinfunction "P$2_2") (pintype "passive"))
      (node (ref "L7") (pin "P$2") (pinfunction "2_P$2") (pintype "passive"))
      (node (ref "R14") (pin "1") (pinfunction "1_1") (pintype "passive"))
      (node (ref "R16") (pin "1") (pinfunction "1_1") (pintype "passive"))
      (node (ref "R23") (pin "1") (pinfunction "1_1") (pintype "passive"))
      (node (ref "U$3") (pin "10") (pinfunction "VIN1_10") (pintype "bidirectional"))
      (node (ref "U$3") (pin "11") (pinfunction "VIN2_11") (pintype "bidirectional"))
      (node (ref "U$6") (pin "A1") (pinfunction "VIN_A1") (pintype "bidirectional"))
      (node (ref "U1") (pin "15") (pinfunction "SYS_15") (pintype "power_in"))
      (node (ref "U1") (pin "16") (pinfunction "SYS_16") (pintype "power_in"))
    )
    (net (code "38") (name "~{CE}") (class "Default")
      (node (ref "R10") (pin "2") (pinfunction "2_2") (pintype "passive"))
      (node (ref "U1") (pin "9") (pinfunction "~{CE}_9") (pintype "output"))
    )
    (net (code "39") (name "~{FUEL-INT}") (class "Default")
      (node (ref "R2") (pin "2") (pinfunction "2_2") (pintype "passive"))
      (node (ref "U$1") (pin "4") (pinfunction "4_4") (pintype "passive"))
      (node (ref "U$1") (pin "@4") (pinfunction "4_@4") (pintype "passive"))
      (node (ref "U1") (pin "7") (pinfunction "INT_7") (pintype "bidirectional"))
      (node (ref "U4") (pin "5") (pinfunction "ALT_5") (pintype "bidirectional"))
    )
    (net (code "40") (name "~{RST}") (class "Default")
      (node (ref "U$1") (pin "11") (pinfunction "11_11") (pintype "passive"))
      (node (ref "U$1") (pin "@11") (pinfunction "11_@11") (pintype "passive"))
    )
  )
)
